# OS_Siding_Board_schematic.net
KiCad netlist of a schematic drawn in EasyEDA
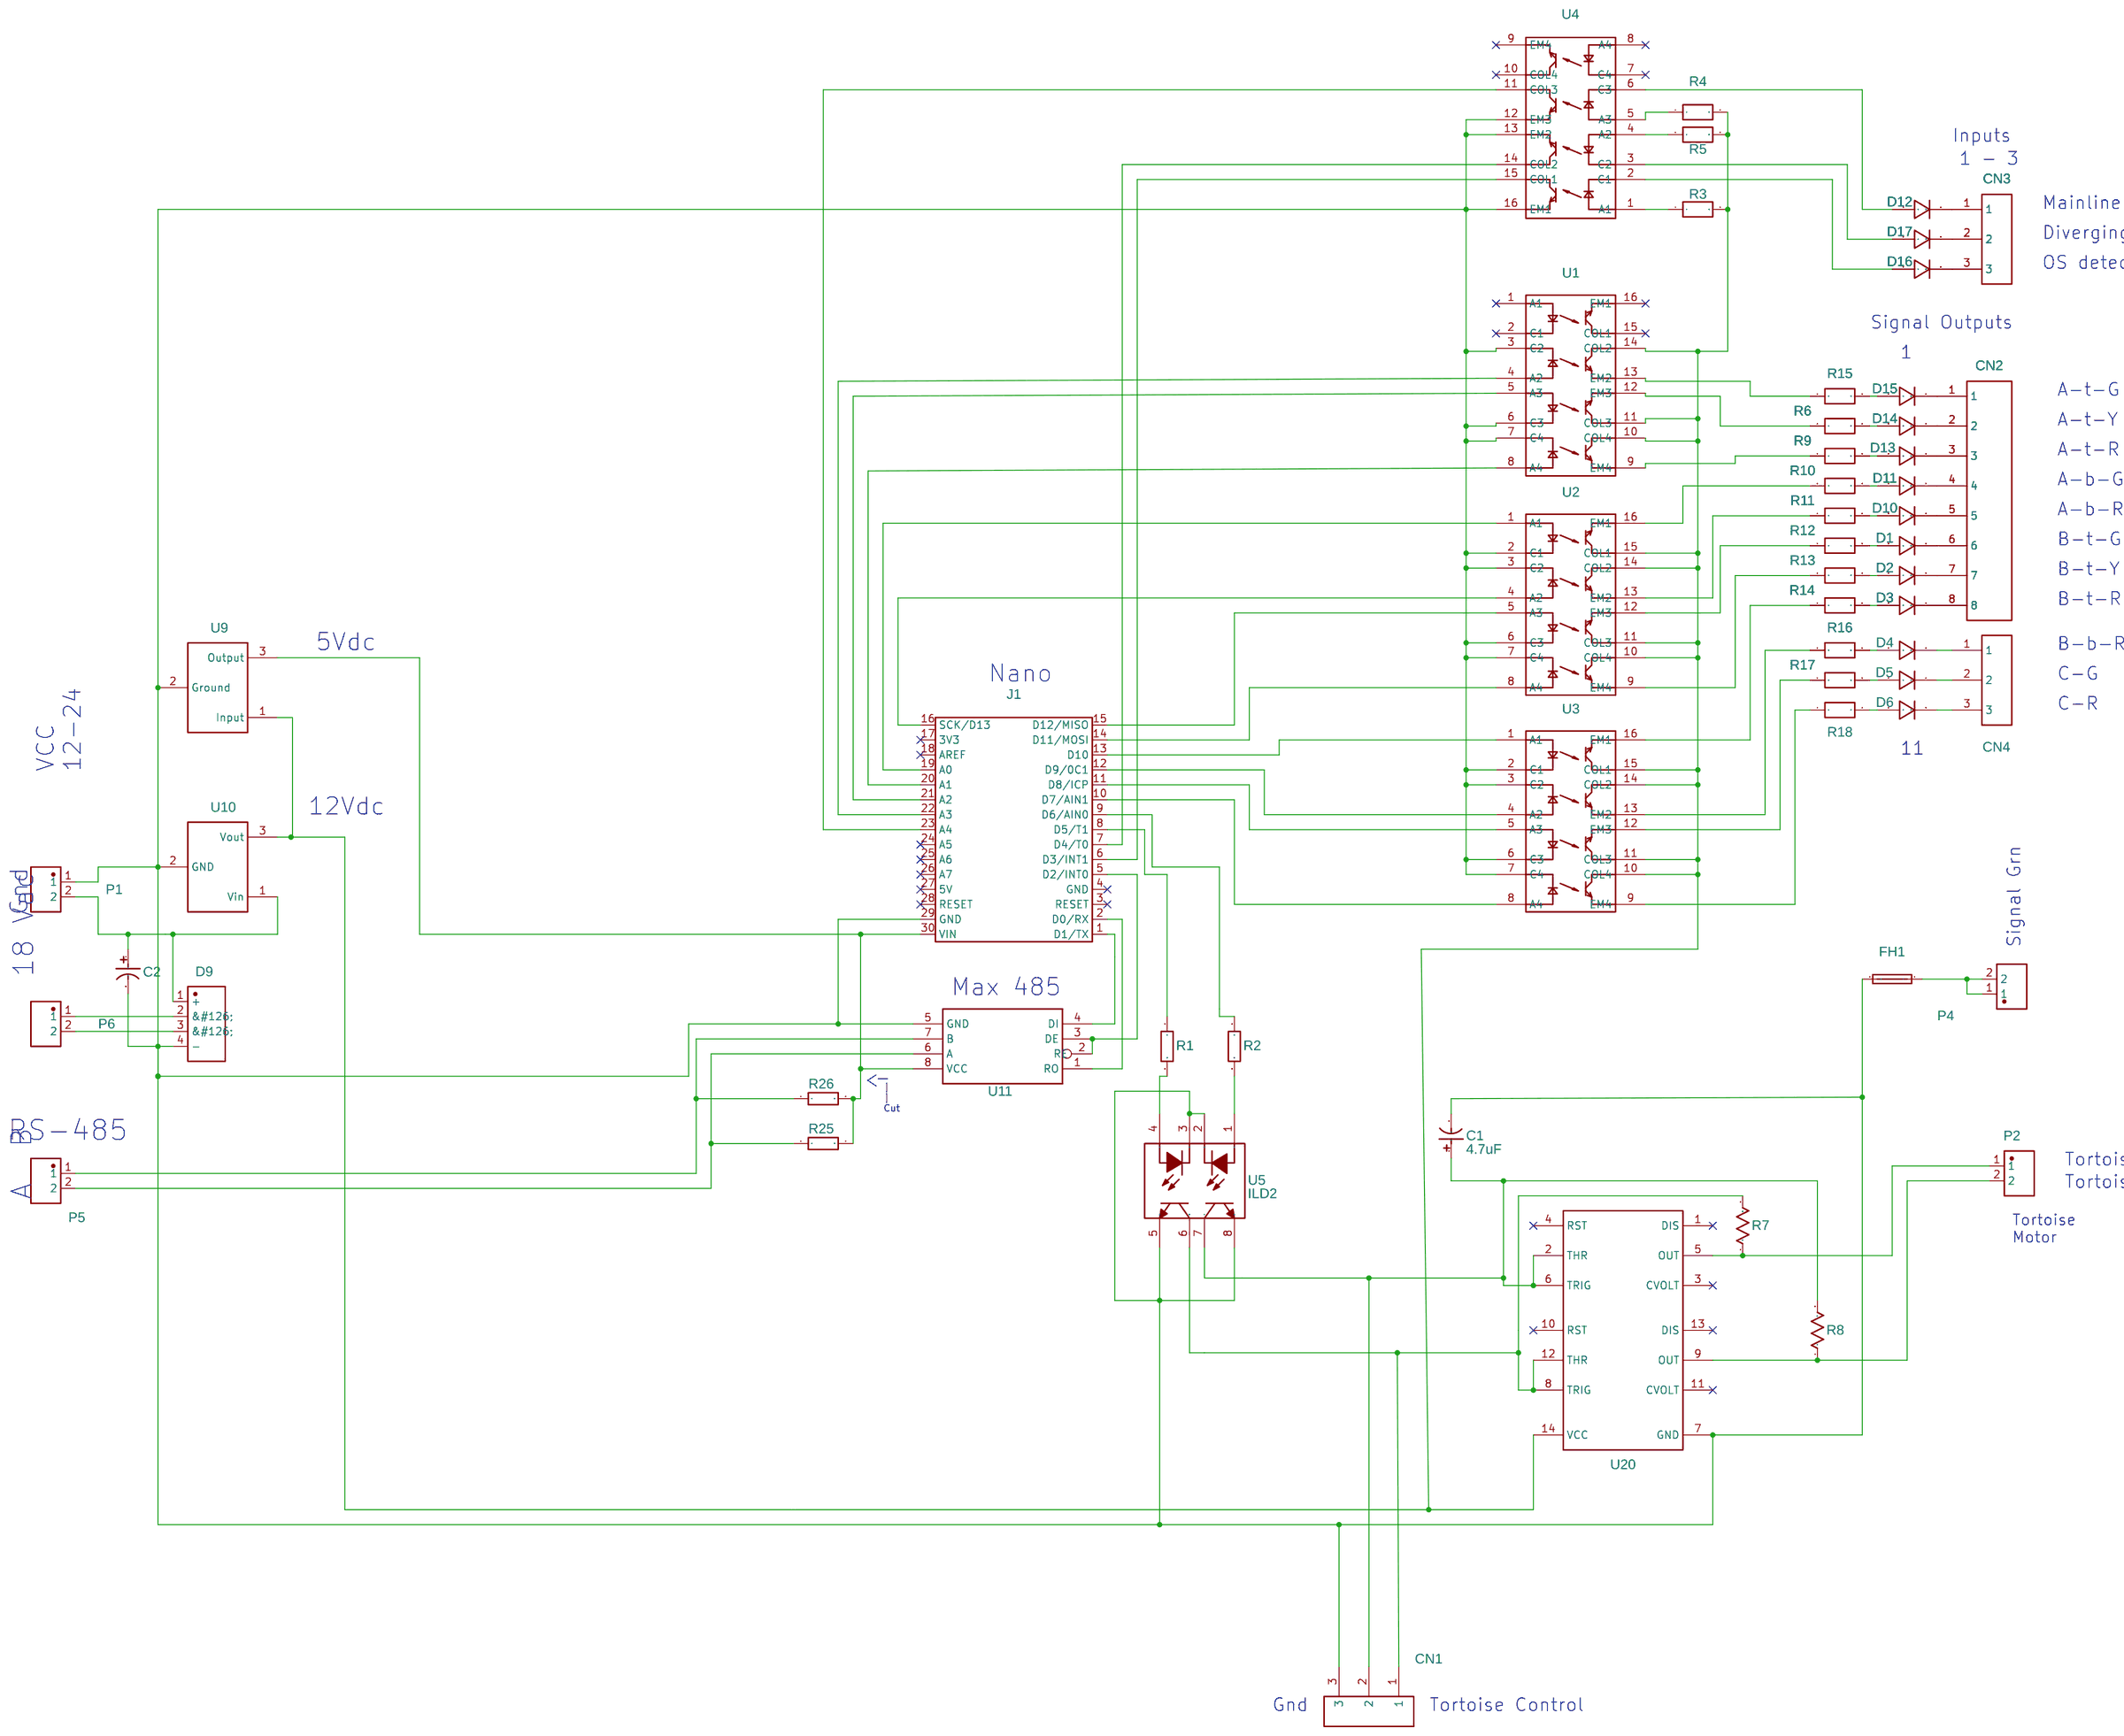
[diagram p0: schematic sheet]

(export (version "E")
  (design (tool "Eeschema 10.0.6"))
  (components
    (comp (ref "C1")
      (value "4.7uF")
      (fields
        (field (name "BOM_Manufacturer Part") "4.7uF 50V 4*7")
        (field (name "BOM_Supplier Part") "C43841")
      )
      (libsource (lib "") (part "4.7uF 50V 4*7"))
    )
    (comp (ref "C2")
      (value "470uF")
      (fields
        (field (name "BOM_Manufacturer Part") "470uF 100V 16*25")
        (field (name "BOM_Supplier Part") "C72551")
      )
      (libsource (lib "") (part "470uF 100V 16*25"))
    )
    (comp (ref "CN1")
      (value "WJ25C-B-7.62-3P-13-00A")
      (fields (field (name "BOM_Supplier Part") "C61583"))
      (libsource (lib "") (part "WJ25C-B-7.62-3P-13-00A_1"))
    )
    (comp (ref "CN2")
      (value "WJ25C-B-7.62-8P-13-00A")
      (fields (field (name "BOM_Supplier Part") "C49492"))
      (libsource (lib "") (part "Unknown_1245_155"))
    )
    (comp (ref "CN3")
      (value "WJ25C-B-7.62-3P-13-00A")
      (fields (field (name "BOM_Supplier Part") "C61583"))
      (libsource (lib "") (part "WJ25C-B-7.62-3P-13-00A"))
    )
    (comp (ref "CN4")
      (value "WJ25C-B-7.62-3P-13-00A")
      (fields (field (name "BOM_Supplier Part") "C61583"))
      (libsource (lib "") (part "WJ25C-B-7.62-3P-13-00A"))
    )
    (comp (ref "D1")
      (value "1N4001")
      (fields (field (name "BOM_Supplier Part") "C169150"))
      (libsource (lib "") (part "Unknown_1205_185"))
    )
    (comp (ref "D2")
      (value "1N4001")
      (fields (field (name "BOM_Supplier Part") "C169150"))
      (libsource (lib "") (part "Unknown_1205_205"))
    )
    (comp (ref "D3")
      (value "1N4001")
      (fields (field (name "BOM_Supplier Part") "C169150"))
      (libsource (lib "") (part "Unknown_1205_225"))
    )
    (comp (ref "D4")
      (value "1N4001")
      (fields (field (name "BOM_Supplier Part") "C169150"))
      (libsource (lib "") (part "Unknown_1205_255"))
    )
    (comp (ref "D5")
      (value "1N4001")
      (fields (field (name "BOM_Supplier Part") "C169150"))
      (libsource (lib "") (part "Unknown_1205_275"))
    )
    (comp (ref "D6")
      (value "1N4001")
      (fields (field (name "BOM_Supplier Part") "C169150"))
      (libsource (lib "") (part "Unknown_1205_295"))
    )
    (comp (ref "D9")
      (value "D50SB100")
      (fields (field (name "BOM_Supplier Part") "C411148"))
      (libsource (lib "") (part "Unknown_60_505"))
    )
    (comp (ref "D10")
      (value "1N4001")
      (fields (field (name "BOM_Supplier Part") "C169150"))
      (libsource (lib "") (part "Unknown_1205_165"))
    )
    (comp (ref "D11")
      (value "1N4001")
      (fields (field (name "BOM_Supplier Part") "C169150"))
      (libsource (lib "") (part "Unknown_1205_145"))
    )
    (comp (ref "D12")
      (value "1N4001")
      (fields (field (name "BOM_Supplier Part") "C169150"))
      (libsource (lib "") (part "Unknown_1215_-40"))
    )
    (comp (ref "D13")
      (value "1N4001")
      (fields (field (name "BOM_Supplier Part") "C169150"))
      (libsource (lib "") (part "Unknown_1205_125"))
    )
    (comp (ref "D14")
      (value "1N4001")
      (fields (field (name "BOM_Supplier Part") "C169150"))
      (libsource (lib "") (part "Unknown_1205_105"))
    )
    (comp (ref "D15")
      (value "1N4001")
      (fields (field (name "BOM_Supplier Part") "C169150"))
      (libsource (lib "") (part "Unknown_1205_85"))
    )
    (comp (ref "D16")
      (value "1N4001")
      (fields (field (name "BOM_Supplier Part") "C169150"))
      (libsource (lib "") (part "Unknown_1215_0"))
    )
    (comp (ref "D17")
      (value "1N4001")
      (fields (field (name "BOM_Supplier Part") "C169150"))
      (libsource (lib "") (part "Unknown_1215_-20"))
    )
    (comp (ref "FH1")
      (value "64600001003")
      (fields (field (name "BOM_Supplier Part") "C206887"))
      (libsource (lib "") (part "Unknown_1195_475"))
    )
    (comp (ref "J1") (value "Arduino_Nano_Header") (libsource (lib "") (part "Unknown_605_375")))
    (comp (ref "P1")
      (value "WJ25C-B-2P")
      (fields (field (name "BOM_Supplier Part") "C8422"))
      (libsource (lib "") (part "Unknown_-40_415"))
    )
    (comp (ref "P2")
      (value "WJ25C-B-2P")
      (fields (field (name "BOM_Supplier Part") "C8422"))
      (libsource (lib "") (part "Unknown_1280_605"))
    )
    (comp (ref "P4")
      (value "WJ25C-B-2P")
      (fields (field (name "BOM_Supplier Part") "C8422"))
      (libsource (lib "") (part "Unknown_1275_480"))
    )
    (comp (ref "P5")
      (value "WJ25C-B-2P")
      (fields (field (name "BOM_Supplier Part") "C8422"))
      (libsource (lib "") (part "Unknown_-40_610"))
    )
    (comp (ref "P6")
      (value "WJ25C-B-2P")
      (fields (field (name "BOM_Supplier Part") "C8422"))
      (libsource (lib "") (part "Unknown_-40_505"))
    )
    (comp (ref "R1")
      (value "150")
      (fields
        (field (name "BOM_Manufacturer Part") "CFR0W4J0151A50")
        (field (name "BOM_Supplier Part") "C70814")
      )
      (libsource (lib "") (part "CFR0W4J0151A50"))
    )
    (comp (ref "R2")
      (value "150")
      (fields
        (field (name "BOM_Manufacturer Part") "CFR0W4J0151A50")
        (field (name "BOM_Supplier Part") "C70814")
      )
      (libsource (lib "") (part "CFR0W4J0151A50"))
    )
    (comp (ref "R3")
      (value "680")
      (fields
        (field (name "BOM_Manufacturer Part") "RD 1/4W 680R J T/B A1")
        (field (name "BOM_Supplier Part") "C433698")
      )
      (libsource (lib "") (part "RD 1/4W 680R J T/B A1"))
    )
    (comp (ref "R4")
      (value "680")
      (fields
        (field (name "BOM_Manufacturer Part") "RD 1/4W 680R J T/B A1")
        (field (name "BOM_Supplier Part") "C433698")
      )
      (libsource (lib "") (part "RD 1/4W 680R J T/B A1"))
    )
    (comp (ref "R5")
      (value "680")
      (fields
        (field (name "BOM_Manufacturer Part") "RD 1/4W 680R J T/B A1")
        (field (name "BOM_Supplier Part") "C433698")
      )
      (libsource (lib "") (part "RD 1/4W 680R J T/B A1"))
    )
    (comp (ref "R6")
      (value "390")
      (fields
        (field (name "BOM_Manufacturer Part") "RD 1/4W 390R J T/B A1")
        (field (name "BOM_Supplier Part") "C433722")
      )
      (libsource (lib "") (part "RD 1/4W 390R J T/B A1"))
    )
    (comp (ref "R7")
      (value "10k")
      (fields
        (field (name "BOM_Manufacturer Part") "RESISTOR_ALONG")
        (field (name "BOM_Supplier Part") "9339116")
      )
      (libsource (lib "") (part "Unknown_1095_640"))
    )
    (comp (ref "R8")
      (value "10k")
      (fields
        (field (name "BOM_Manufacturer Part") "RESISTOR_ALONG")
        (field (name "BOM_Supplier Part") "9339116")
      )
      (libsource (lib "") (part "Unknown_1145_710"))
    )
    (comp (ref "R9")
      (value "390")
      (fields
        (field (name "BOM_Manufacturer Part") "RD 1/4W 390R J T/B A1")
        (field (name "BOM_Supplier Part") "C433722")
      )
      (libsource (lib "") (part "RD 1/4W 390R J T/B A1"))
    )
    (comp (ref "R10")
      (value "390")
      (fields
        (field (name "BOM_Manufacturer Part") "RD 1/4W 390R J T/B A1")
        (field (name "BOM_Supplier Part") "C433722")
      )
      (libsource (lib "") (part "RD 1/4W 390R J T/B A1"))
    )
    (comp (ref "R11")
      (value "390")
      (fields
        (field (name "BOM_Manufacturer Part") "RD 1/4W 390R J T/B A1")
        (field (name "BOM_Supplier Part") "C433722")
      )
      (libsource (lib "") (part "RD 1/4W 390R J T/B A1"))
    )
    (comp (ref "R12")
      (value "390")
      (fields
        (field (name "BOM_Manufacturer Part") "RD 1/4W 390R J T/B A1")
        (field (name "BOM_Supplier Part") "C433722")
      )
      (libsource (lib "") (part "RD 1/4W 390R J T/B A1"))
    )
    (comp (ref "R13")
      (value "390")
      (fields
        (field (name "BOM_Manufacturer Part") "RD 1/4W 390R J T/B A1")
        (field (name "BOM_Supplier Part") "C433722")
      )
      (libsource (lib "") (part "RD 1/4W 390R J T/B A1"))
    )
    (comp (ref "R14")
      (value "390")
      (fields
        (field (name "BOM_Manufacturer Part") "RD 1/4W 390R J T/B A1")
        (field (name "BOM_Supplier Part") "C433722")
      )
      (libsource (lib "") (part "RD 1/4W 390R J T/B A1"))
    )
    (comp (ref "R15")
      (value "390")
      (fields
        (field (name "BOM_Manufacturer Part") "RD 1/4W 390R J T/B A1")
        (field (name "BOM_Supplier Part") "C433722")
      )
      (libsource (lib "") (part "RD 1/4W 390R J T/B A1"))
    )
    (comp (ref "R16")
      (value "390")
      (fields
        (field (name "BOM_Manufacturer Part") "RD 1/4W 390R J T/B A1")
        (field (name "BOM_Supplier Part") "C433722")
      )
      (libsource (lib "") (part "RD 1/4W 390R J T/B A1"))
    )
    (comp (ref "R17")
      (value "390")
      (fields
        (field (name "BOM_Manufacturer Part") "RD 1/4W 390R J T/B A1")
        (field (name "BOM_Supplier Part") "C433722")
      )
      (libsource (lib "") (part "RD 1/4W 390R J T/B A1"))
    )
    (comp (ref "R18")
      (value "390")
      (fields
        (field (name "BOM_Manufacturer Part") "RD 1/4W 390R J T/B A1")
        (field (name "BOM_Supplier Part") "C433722")
      )
      (libsource (lib "") (part "RD 1/4W 390R J T/B A1"))
    )
    (comp (ref "R25")
      (value "10K")
      (fields
        (field (name "BOM_Manufacturer Part") "CFR0W4J0103A50")
        (field (name "BOM_Supplier Part") "C61299")
      )
      (libsource (lib "") (part "CFR0W4J0103A50"))
    )
    (comp (ref "R26")
      (value "10K")
      (fields
        (field (name "BOM_Manufacturer Part") "CFR0W4J0103A50")
        (field (name "BOM_Supplier Part") "C61299")
      )
      (libsource (lib "") (part "CFR0W4J0103A50"))
    )
    (comp (ref "U1")
      (value "ILQ2")
      (fields (field (name "BOM_Supplier Part") "C145338"))
      (libsource (lib "") (part "ILQ2_1"))
    )
    (comp (ref "U2")
      (value "ILQ2")
      (fields (field (name "BOM_Supplier Part") "C145338"))
      (libsource (lib "") (part "ILQ2"))
    )
    (comp (ref "U3")
      (value "ILQ2")
      (fields (field (name "BOM_Supplier Part") "C145338"))
      (libsource (lib "") (part "ILQ2"))
    )
    (comp (ref "U4")
      (value "ILQ2")
      (fields (field (name "BOM_Supplier Part") "C145338"))
      (libsource (lib "") (part "ILQ2_2"))
    )
    (comp (ref "U5")
      (value "ILD2")
      (fields (field (name "BOM_Supplier Part") "C10612"))
      (libsource (lib "") (part "ILD2"))
    )
    (comp (ref "U9")
      (value "MC7805BTG")
      (fields (field (name "BOM_Supplier Part") "C45385"))
      (libsource (lib "") (part "Unknown_75_280"))
    )
    (comp (ref "U10")
      (value "CJ7812")
      (fields (field (name "BOM_Supplier Part") "C77894"))
      (libsource (lib "") (part "Unknown_75_400"))
    )
    (comp (ref "U11") (value "MAX485DIL") (libsource (lib "") (part "Unknown_600_520")))
    (comp (ref "U20")
      (value "LM556CN")
      (fields (field (name "BOM_Manufacturer Part") "?"))
      (libsource (lib "") (part "Unknown_1015_710"))
    )
  )
  (nets
    (net (code "1") (name "Net-(C1-Pad1)") (class "Default")
      (node (ref "C1") (pin "1") (pinfunction "1_1") (pintype "input"))
      (node (ref "CN1") (pin "2") (pinfunction "2_2") (pintype "input"))
      (node (ref "R8") (pin "2") (pinfunction "2_2") (pintype "unspecified"))
      (node (ref "U20") (pin "2") (pinfunction "THR_2") (pintype "unspecified"))
      (node (ref "U20") (pin "6") (pinfunction "TRIG_6") (pintype "unspecified"))
      (node (ref "U5") (pin "7") (pinfunction "7_7") (pintype "unspecified"))
    )
    (net (code "2") (name "Net-(CN1-Pad1)") (class "Default")
      (node (ref "CN1") (pin "1") (pinfunction "1_1") (pintype "input"))
      (node (ref "R7") (pin "2") (pinfunction "2_2") (pintype "unspecified"))
      (node (ref "U20") (pin "12") (pinfunction "THR_12") (pintype "unspecified"))
      (node (ref "U20") (pin "8") (pinfunction "TRIG_8") (pintype "unspecified"))
      (node (ref "U5") (pin "6") (pinfunction "6_6") (pintype "unspecified"))
    )
    (net (code "3") (name "Net-(CN2-Pad1)") (class "Default")
      (node (ref "CN2") (pin "1") (pinfunction "1_1") (pintype "input"))
      (node (ref "D15") (pin "2") (pinfunction "2_2") (pintype "unspecified"))
    )
    (net (code "4") (name "Net-(CN2-Pad2)") (class "Default")
      (node (ref "CN2") (pin "2") (pinfunction "2_2") (pintype "input"))
      (node (ref "D14") (pin "2") (pinfunction "2_2") (pintype "unspecified"))
    )
    (net (code "5") (name "Net-(CN2-Pad3)") (class "Default")
      (node (ref "CN2") (pin "3") (pinfunction "3_3") (pintype "input"))
      (node (ref "D13") (pin "2") (pinfunction "2_2") (pintype "unspecified"))
    )
    (net (code "6") (name "Net-(CN2-Pad4)") (class "Default")
      (node (ref "CN2") (pin "4") (pinfunction "4_4") (pintype "input"))
      (node (ref "D11") (pin "2") (pinfunction "2_2") (pintype "unspecified"))
    )
    (net (code "7") (name "Net-(CN2-Pad5)") (class "Default")
      (node (ref "CN2") (pin "5") (pinfunction "5_5") (pintype "input"))
      (node (ref "D10") (pin "2") (pinfunction "2_2") (pintype "unspecified"))
    )
    (net (code "8") (name "Net-(CN2-Pad6)") (class "Default")
      (node (ref "CN2") (pin "6") (pinfunction "6_6") (pintype "input"))
      (node (ref "D1") (pin "2") (pinfunction "2_2") (pintype "unspecified"))
    )
    (net (code "9") (name "Net-(CN2-Pad7)") (class "Default")
      (node (ref "CN2") (pin "7") (pinfunction "7_7") (pintype "input"))
      (node (ref "D2") (pin "2") (pinfunction "2_2") (pintype "unspecified"))
    )
    (net (code "10") (name "Net-(CN2-Pad8)") (class "Default")
      (node (ref "CN2") (pin "8") (pinfunction "8_8") (pintype "input"))
      (node (ref "D3") (pin "2") (pinfunction "2_2") (pintype "unspecified"))
    )
    (net (code "11") (name "Net-(CN3-Pad1)") (class "Default")
      (node (ref "CN3") (pin "1") (pinfunction "1_1") (pintype "input"))
      (node (ref "D12") (pin "2") (pinfunction "2_2") (pintype "unspecified"))
    )
    (net (code "12") (name "Net-(CN3-Pad2)") (class "Default")
      (node (ref "CN3") (pin "2") (pinfunction "2_2") (pintype "input"))
      (node (ref "D17") (pin "2") (pinfunction "2_2") (pintype "unspecified"))
    )
    (net (code "13") (name "Net-(CN3-Pad3)") (class "Default")
      (node (ref "CN3") (pin "3") (pinfunction "3_3") (pintype "input"))
      (node (ref "D16") (pin "2") (pinfunction "2_2") (pintype "unspecified"))
    )
    (net (code "14") (name "Net-(CN4-Pad1)") (class "Default")
      (node (ref "CN4") (pin "1") (pinfunction "1_1") (pintype "input"))
      (node (ref "D4") (pin "2") (pinfunction "2_2") (pintype "unspecified"))
    )
    (net (code "15") (name "Net-(CN4-Pad2)") (class "Default")
      (node (ref "CN4") (pin "2") (pinfunction "2_2") (pintype "input"))
      (node (ref "D5") (pin "2") (pinfunction "2_2") (pintype "unspecified"))
    )
    (net (code "16") (name "Net-(CN4-Pad3)") (class "Default")
      (node (ref "CN4") (pin "3") (pinfunction "3_3") (pintype "input"))
      (node (ref "D6") (pin "2") (pinfunction "2_2") (pintype "unspecified"))
    )
    (net (code "17") (name "Net-(D1-Pad1)") (class "Default")
      (node (ref "D1") (pin "1") (pinfunction "1_1") (pintype "unspecified"))
      (node (ref "R12") (pin "2") (pinfunction "2_2") (pintype "unspecified"))
    )
    (net (code "18") (name "Net-(D2-Pad1)") (class "Default")
      (node (ref "D2") (pin "1") (pinfunction "1_1") (pintype "unspecified"))
      (node (ref "R13") (pin "2") (pinfunction "2_2") (pintype "unspecified"))
    )
    (net (code "19") (name "Net-(D3-Pad1)") (class "Default")
      (node (ref "D3") (pin "1") (pinfunction "1_1") (pintype "unspecified"))
      (node (ref "R14") (pin "2") (pinfunction "2_2") (pintype "unspecified"))
    )
    (net (code "20") (name "Net-(D4-Pad1)") (class "Default")
      (node (ref "D4") (pin "1") (pinfunction "1_1") (pintype "unspecified"))
      (node (ref "R16") (pin "2") (pinfunction "2_2") (pintype "unspecified"))
    )
    (net (code "21") (name "Net-(D5-Pad1)") (class "Default")
      (node (ref "D5") (pin "1") (pinfunction "1_1") (pintype "unspecified"))
      (node (ref "R17") (pin "2") (pinfunction "2_2") (pintype "unspecified"))
    )
    (net (code "22") (name "Net-(D6-Pad1)") (class "Default")
      (node (ref "D6") (pin "1") (pinfunction "1_1") (pintype "unspecified"))
      (node (ref "R18") (pin "2") (pinfunction "2_2") (pintype "unspecified"))
    )
    (net (code "23") (name "Net-(D9-&#126;-Pad2)") (class "Default")
      (node (ref "D9") (pin "2") (pinfunction "&#126;_2") (pintype "unspecified"))
      (node (ref "P6") (pin "1") (pinfunction "1_1") (pintype "unspecified"))
    )
    (net (code "24") (name "Net-(D9-&#126;-Pad3)") (class "Default")
      (node (ref "D9") (pin "3") (pinfunction "&#126;_3") (pintype "unspecified"))
      (node (ref "P6") (pin "2") (pinfunction "2_2") (pintype "unspecified"))
    )
    (net (code "25") (name "Net-(D9-+)") (class "Default")
      (node (ref "C2") (pin "1") (pinfunction "1_1") (pintype "input"))
      (node (ref "D9") (pin "1") (pinfunction "+_1") (pintype "unspecified"))
      (node (ref "P1") (pin "2") (pinfunction "2_2") (pintype "unspecified"))
      (node (ref "U10") (pin "1") (pinfunction "Vin_1") (pintype "unspecified"))
    )
    (net (code "26") (name "Net-(D9--)") (class "Default")
      (node (ref "C1") (pin "2") (pinfunction "2_2") (pintype "input"))
      (node (ref "C2") (pin "2") (pinfunction "2_2") (pintype "input"))
      (node (ref "CN1") (pin "3") (pinfunction "3_3") (pintype "input"))
      (node (ref "D9") (pin "4") (pinfunction "-_4") (pintype "unspecified"))
      (node (ref "FH1") (pin "2") (pinfunction "2_2") (pintype "unspecified"))
      (node (ref "J1") (pin "29") (pinfunction "GND_29") (pintype "unspecified"))
      (node (ref "P1") (pin "1") (pinfunction "1_1") (pintype "unspecified"))
      (node (ref "U1") (pin "3") (pinfunction "C2_3") (pintype "unspecified"))
      (node (ref "U1") (pin "6") (pinfunction "C3_6") (pintype "unspecified"))
      (node (ref "U1") (pin "7") (pinfunction "C4_7") (pintype "unspecified"))
      (node (ref "U10") (pin "2") (pinfunction "GND_2") (pintype "unspecified"))
      (node (ref "U11") (pin "5") (pinfunction "GND_5") (pintype "unspecified"))
      (node (ref "U2") (pin "2") (pinfunction "C1_2") (pintype "unspecified"))
      (node (ref "U2") (pin "3") (pinfunction "C2_3") (pintype "unspecified"))
      (node (ref "U2") (pin "6") (pinfunction "C3_6") (pintype "unspecified"))
      (node (ref "U2") (pin "7") (pinfunction "C4_7") (pintype "unspecified"))
      (node (ref "U20") (pin "7") (pinfunction "GND_7") (pintype "passive"))
      (node (ref "U3") (pin "2") (pinfunction "C1_2") (pintype "unspecified"))
      (node (ref "U3") (pin "3") (pinfunction "C2_3") (pintype "unspecified"))
      (node (ref "U3") (pin "6") (pinfunction "C3_6") (pintype "unspecified"))
      (node (ref "U3") (pin "7") (pinfunction "C4_7") (pintype "unspecified"))
      (node (ref "U4") (pin "12") (pinfunction "EM3_12") (pintype "unspecified"))
      (node (ref "U4") (pin "13") (pinfunction "EM2_13") (pintype "unspecified"))
      (node (ref "U4") (pin "16") (pinfunction "EM1_16") (pintype "unspecified"))
      (node (ref "U5") (pin "2") (pinfunction "2_2") (pintype "unspecified"))
      (node (ref "U5") (pin "3") (pinfunction "3_3") (pintype "unspecified"))
      (node (ref "U5") (pin "5") (pinfunction "5_5") (pintype "unspecified"))
      (node (ref "U5") (pin "8") (pinfunction "8_8") (pintype "unspecified"))
      (node (ref "U9") (pin "2") (pinfunction "Ground_2") (pintype "unspecified"))
    )
    (net (code "27") (name "Net-(D10-Pad1)") (class "Default")
      (node (ref "D10") (pin "1") (pinfunction "1_1") (pintype "unspecified"))
      (node (ref "R11") (pin "2") (pinfunction "2_2") (pintype "unspecified"))
    )
    (net (code "28") (name "Net-(D11-Pad1)") (class "Default")
      (node (ref "D11") (pin "1") (pinfunction "1_1") (pintype "unspecified"))
      (node (ref "R10") (pin "2") (pinfunction "2_2") (pintype "unspecified"))
    )
    (net (code "29") (name "Net-(D13-Pad1)") (class "Default")
      (node (ref "D13") (pin "1") (pinfunction "1_1") (pintype "unspecified"))
      (node (ref "R9") (pin "2") (pinfunction "2_2") (pintype "unspecified"))
    )
    (net (code "30") (name "Net-(D14-Pad1)") (class "Default")
      (node (ref "D14") (pin "1") (pinfunction "1_1") (pintype "unspecified"))
      (node (ref "R6") (pin "2") (pinfunction "2_2") (pintype "unspecified"))
    )
    (net (code "31") (name "Net-(D15-Pad1)") (class "Default")
      (node (ref "D15") (pin "1") (pinfunction "1_1") (pintype "unspecified"))
      (node (ref "R15") (pin "2") (pinfunction "2_2") (pintype "unspecified"))
    )
    (net (code "32") (name "Net-(FH1-Pad1)") (class "Default")
      (node (ref "FH1") (pin "1") (pinfunction "1_1") (pintype "unspecified"))
      (node (ref "P4") (pin "1") (pinfunction "1_1") (pintype "unspecified"))
      (node (ref "P4") (pin "2") (pinfunction "2_2") (pintype "unspecified"))
    )
    (net (code "33") (name "Net-(J1-A0)") (class "Default")
      (node (ref "J1") (pin "19") (pinfunction "A0_19") (pintype "unspecified"))
      (node (ref "U2") (pin "1") (pinfunction "A1_1") (pintype "unspecified"))
    )
    (net (code "34") (name "Net-(J1-A1)") (class "Default")
      (node (ref "J1") (pin "20") (pinfunction "A1_20") (pintype "unspecified"))
      (node (ref "U1") (pin "8") (pinfunction "A4_8") (pintype "unspecified"))
    )
    (net (code "35") (name "Net-(J1-A2)") (class "Default")
      (node (ref "J1") (pin "21") (pinfunction "A2_21") (pintype "unspecified"))
      (node (ref "U1") (pin "5") (pinfunction "A3_5") (pintype "unspecified"))
    )
    (net (code "36") (name "Net-(J1-A3)") (class "Default")
      (node (ref "J1") (pin "22") (pinfunction "A3_22") (pintype "unspecified"))
      (node (ref "U1") (pin "4") (pinfunction "A2_4") (pintype "unspecified"))
    )
    (net (code "37") (name "Net-(J1-A4)") (class "Default")
      (node (ref "J1") (pin "23") (pinfunction "A4_23") (pintype "unspecified"))
      (node (ref "U4") (pin "11") (pinfunction "COL3_11") (pintype "unspecified"))
    )
    (net (code "38") (name "Net-(J1-D0{slash}RX)") (class "Default")
      (node (ref "J1") (pin "2") (pinfunction "D0/RX_2") (pintype "unspecified"))
      (node (ref "U11") (pin "1") (pinfunction "RO_1") (pintype "unspecified"))
    )
    (net (code "39") (name "Net-(J1-D1{slash}TX)") (class "Default")
      (node (ref "J1") (pin "1") (pinfunction "D1/TX_1") (pintype "unspecified"))
      (node (ref "U11") (pin "4") (pinfunction "DI_4") (pintype "unspecified"))
    )
    (net (code "40") (name "Net-(J1-D2{slash}INT0)") (class "Default")
      (node (ref "J1") (pin "5") (pinfunction "D2/INT0_5") (pintype "unspecified"))
      (node (ref "U11") (pin "2") (pinfunction "RE_2") (pintype "unspecified"))
      (node (ref "U11") (pin "3") (pinfunction "DE_3") (pintype "unspecified"))
    )
    (net (code "41") (name "Net-(J1-D3{slash}INT1)") (class "Default")
      (node (ref "J1") (pin "6") (pinfunction "D3/INT1_6") (pintype "unspecified"))
      (node (ref "U4") (pin "15") (pinfunction "COL1_15") (pintype "unspecified"))
    )
    (net (code "42") (name "Net-(J1-D4{slash}T0)") (class "Default")
      (node (ref "J1") (pin "7") (pinfunction "D4/T0_7") (pintype "unspecified"))
      (node (ref "U4") (pin "14") (pinfunction "COL2_14") (pintype "unspecified"))
    )
    (net (code "43") (name "Net-(J1-D5{slash}T1)") (class "Default")
      (node (ref "J1") (pin "8") (pinfunction "D5/T1_8") (pintype "unspecified"))
      (node (ref "R1") (pin "1") (pinfunction "1_1") (pintype "input"))
    )
    (net (code "44") (name "Net-(J1-D6{slash}AIN0)") (class "Default")
      (node (ref "J1") (pin "9") (pinfunction "D6/AIN0_9") (pintype "unspecified"))
      (node (ref "R2") (pin "1") (pinfunction "1_1") (pintype "input"))
    )
    (net (code "45") (name "Net-(J1-D7{slash}AIN1)") (class "Default")
      (node (ref "J1") (pin "10") (pinfunction "D7/AIN1_10") (pintype "unspecified"))
      (node (ref "U3") (pin "8") (pinfunction "A4_8") (pintype "unspecified"))
    )
    (net (code "46") (name "Net-(J1-D8{slash}ICP)") (class "Default")
      (node (ref "J1") (pin "11") (pinfunction "D8/ICP_11") (pintype "unspecified"))
      (node (ref "U3") (pin "5") (pinfunction "A3_5") (pintype "unspecified"))
    )
    (net (code "47") (name "Net-(J1-D9{slash}0C1)") (class "Default")
      (node (ref "J1") (pin "12") (pinfunction "D9/0C1_12") (pintype "unspecified"))
      (node (ref "U3") (pin "4") (pinfunction "A2_4") (pintype "unspecified"))
    )
    (net (code "48") (name "Net-(J1-D10)") (class "Default")
      (node (ref "J1") (pin "13") (pinfunction "D10_13") (pintype "unspecified"))
      (node (ref "U3") (pin "1") (pinfunction "A1_1") (pintype "unspecified"))
    )
    (net (code "49") (name "Net-(J1-D11{slash}MOSI)") (class "Default")
      (node (ref "J1") (pin "14") (pinfunction "D11/MOSI_14") (pintype "unspecified"))
      (node (ref "U2") (pin "8") (pinfunction "A4_8") (pintype "unspecified"))
    )
    (net (code "50") (name "Net-(J1-D12{slash}MISO)") (class "Default")
      (node (ref "J1") (pin "15") (pinfunction "D12/MISO_15") (pintype "unspecified"))
      (node (ref "U2") (pin "5") (pinfunction "A3_5") (pintype "unspecified"))
    )
    (net (code "51") (name "Net-(J1-SCK{slash}D13)") (class "Default")
      (node (ref "J1") (pin "16") (pinfunction "SCK/D13_16") (pintype "unspecified"))
      (node (ref "U2") (pin "4") (pinfunction "A2_4") (pintype "unspecified"))
    )
    (net (code "52") (name "Net-(J1-VIN)") (class "Default")
      (node (ref "J1") (pin "30") (pinfunction "VIN_30") (pintype "unspecified"))
      (node (ref "R25") (pin "2") (pinfunction "2_2") (pintype "input"))
      (node (ref "R26") (pin "2") (pinfunction "2_2") (pintype "input"))
      (node (ref "U11") (pin "8") (pinfunction "VCC_8") (pintype "unspecified"))
      (node (ref "U9") (pin "3") (pinfunction "Output_3") (pintype "unspecified"))
    )
    (net (code "53") (name "Net-(P2-Pad1)") (class "Default")
      (node (ref "P2") (pin "1") (pinfunction "1_1") (pintype "unspecified"))
      (node (ref "R7") (pin "1") (pinfunction "1_1") (pintype "unspecified"))
      (node (ref "U20") (pin "5") (pinfunction "OUT_5") (pintype "output"))
    )
    (net (code "54") (name "Net-(P2-Pad2)") (class "Default")
      (node (ref "P2") (pin "2") (pinfunction "2_2") (pintype "unspecified"))
      (node (ref "R8") (pin "1") (pinfunction "1_1") (pintype "unspecified"))
      (node (ref "U20") (pin "9") (pinfunction "OUT_9") (pintype "output"))
    )
    (net (code "55") (name "Net-(R1-Pad2)") (class "Default")
      (node (ref "R1") (pin "2") (pinfunction "2_2") (pintype "input"))
      (node (ref "U5") (pin "4") (pinfunction "4_4") (pintype "unspecified"))
    )
    (net (code "56") (name "Net-(R2-Pad2)") (class "Default")
      (node (ref "R2") (pin "2") (pinfunction "2_2") (pintype "input"))
      (node (ref "U5") (pin "1") (pinfunction "1_1") (pintype "unspecified"))
    )
    (net (code "57") (name "Net-(U1-COL2)") (class "Default")
      (node (ref "R3") (pin "2") (pinfunction "2_2") (pintype "unspecified"))
      (node (ref "R4") (pin "2") (pinfunction "2_2") (pintype "unspecified"))
      (node (ref "R5") (pin "2") (pinfunction "2_2") (pintype "unspecified"))
      (node (ref "U1") (pin "10") (pinfunction "COL4_10") (pintype "unspecified"))
      (node (ref "U1") (pin "11") (pinfunction "COL3_11") (pintype "unspecified"))
      (node (ref "U1") (pin "14") (pinfunction "COL2_14") (pintype "unspecified"))
      (node (ref "U10") (pin "3") (pinfunction "Vout_3") (pintype "unspecified"))
      (node (ref "U2") (pin "10") (pinfunction "COL4_10") (pintype "unspecified"))
      (node (ref "U2") (pin "11") (pinfunction "COL3_11") (pintype "unspecified"))
      (node (ref "U2") (pin "14") (pinfunction "COL2_14") (pintype "unspecified"))
      (node (ref "U2") (pin "15") (pinfunction "COL1_15") (pintype "unspecified"))
      (node (ref "U20") (pin "14") (pinfunction "VCC_14") (pintype "passive"))
      (node (ref "U3") (pin "10") (pinfunction "COL4_10") (pintype "unspecified"))
      (node (ref "U3") (pin "11") (pinfunction "COL3_11") (pintype "unspecified"))
      (node (ref "U3") (pin "14") (pinfunction "COL2_14") (pintype "unspecified"))
      (node (ref "U3") (pin "15") (pinfunction "COL1_15") (pintype "unspecified"))
      (node (ref "U9") (pin "1") (pinfunction "Input_1") (pintype "unspecified"))
    )
    (net (code "58") (name "Net-(U1-EM2)") (class "Default")
      (node (ref "R15") (pin "1") (pinfunction "1_1") (pintype "unspecified"))
      (node (ref "U1") (pin "13") (pinfunction "EM2_13") (pintype "unspecified"))
    )
    (net (code "59") (name "Net-(U1-EM3)") (class "Default")
      (node (ref "R6") (pin "1") (pinfunction "1_1") (pintype "unspecified"))
      (node (ref "U1") (pin "12") (pinfunction "EM3_12") (pintype "unspecified"))
    )
    (net (code "60") (name "Net-(U1-EM4)") (class "Default")
      (node (ref "R9") (pin "1") (pinfunction "1_1") (pintype "unspecified"))
      (node (ref "U1") (pin "9") (pinfunction "EM4_9") (pintype "unspecified"))
    )
    (net (code "61") (name "Net-(U2-EM1)") (class "Default")
      (node (ref "R10") (pin "1") (pinfunction "1_1") (pintype "unspecified"))
      (node (ref "U2") (pin "16") (pinfunction "EM1_16") (pintype "unspecified"))
    )
    (net (code "62") (name "Net-(U2-EM2)") (class "Default")
      (node (ref "R11") (pin "1") (pinfunction "1_1") (pintype "unspecified"))
      (node (ref "U2") (pin "13") (pinfunction "EM2_13") (pintype "unspecified"))
    )
    (net (code "63") (name "Net-(U2-EM3)") (class "Default")
      (node (ref "R12") (pin "1") (pinfunction "1_1") (pintype "unspecified"))
      (node (ref "U2") (pin "12") (pinfunction "EM3_12") (pintype "unspecified"))
    )
    (net (code "64") (name "Net-(U2-EM4)") (class "Default")
      (node (ref "R13") (pin "1") (pinfunction "1_1") (pintype "unspecified"))
      (node (ref "U2") (pin "9") (pinfunction "EM4_9") (pintype "unspecified"))
    )
    (net (code "65") (name "Net-(U3-EM1)") (class "Default")
      (node (ref "R14") (pin "1") (pinfunction "1_1") (pintype "unspecified"))
      (node (ref "U3") (pin "16") (pinfunction "EM1_16") (pintype "unspecified"))
    )
    (net (code "66") (name "Net-(U3-EM2)") (class "Default")
      (node (ref "R16") (pin "1") (pinfunction "1_1") (pintype "unspecified"))
      (node (ref "U3") (pin "13") (pinfunction "EM2_13") (pintype "unspecified"))
    )
    (net (code "67") (name "Net-(U3-EM3)") (class "Default")
      (node (ref "R17") (pin "1") (pinfunction "1_1") (pintype "unspecified"))
      (node (ref "U3") (pin "12") (pinfunction "EM3_12") (pintype "unspecified"))
    )
    (net (code "68") (name "Net-(U3-EM4)") (class "Default")
      (node (ref "R18") (pin "1") (pinfunction "1_1") (pintype "unspecified"))
      (node (ref "U3") (pin "9") (pinfunction "EM4_9") (pintype "unspecified"))
    )
    (net (code "69") (name "Net-(U4-A1)") (class "Default")
      (node (ref "R3") (pin "1") (pinfunction "1_1") (pintype "unspecified"))
      (node (ref "U4") (pin "1") (pinfunction "A1_1") (pintype "unspecified"))
    )
    (net (code "70") (name "Net-(U4-A2)") (class "Default")
      (node (ref "R5") (pin "1") (pinfunction "1_1") (pintype "unspecified"))
      (node (ref "U4") (pin "4") (pinfunction "A2_4") (pintype "unspecified"))
    )
    (net (code "71") (name "Net-(U4-A3)") (class "Default")
      (node (ref "R4") (pin "1") (pinfunction "1_1") (pintype "unspecified"))
      (node (ref "U4") (pin "5") (pinfunction "A3_5") (pintype "unspecified"))
    )
    (net (code "72") (name "Net-(U4-C1)") (class "Default")
      (node (ref "D16") (pin "1") (pinfunction "1_1") (pintype "unspecified"))
      (node (ref "U4") (pin "2") (pinfunction "C1_2") (pintype "unspecified"))
    )
    (net (code "73") (name "Net-(U4-C2)") (class "Default")
      (node (ref "D17") (pin "1") (pinfunction "1_1") (pintype "unspecified"))
      (node (ref "U4") (pin "3") (pinfunction "C2_3") (pintype "unspecified"))
    )
    (net (code "74") (name "Net-(U4-C3)") (class "Default")
      (node (ref "D12") (pin "1") (pinfunction "1_1") (pintype "unspecified"))
      (node (ref "U4") (pin "6") (pinfunction "C3_6") (pintype "unspecified"))
    )
    (net (code "75") (name "Net-(U11-A)") (class "Default")
      (node (ref "P5") (pin "2") (pinfunction "2_2") (pintype "unspecified"))
      (node (ref "R25") (pin "1") (pinfunction "1_1") (pintype "input"))
      (node (ref "U11") (pin "6") (pinfunction "A_6") (pintype "unspecified"))
    )
    (net (code "76") (name "Net-(U11-B)") (class "Default")
      (node (ref "P5") (pin "1") (pinfunction "1_1") (pintype "unspecified"))
      (node (ref "R26") (pin "1") (pinfunction "1_1") (pintype "input"))
      (node (ref "U11") (pin "7") (pinfunction "B_7") (pintype "unspecified"))
    )
    (net (code "77") (name "unconnected-(J1-3V3-Pad17)") (class "Default")
      (node (ref "J1") (pin "17") (pinfunction "3V3_17") (pintype "unspecified+no_connect"))
    )
    (net (code "78") (name "unconnected-(J1-5V-Pad27)") (class "Default")
      (node (ref "J1") (pin "27") (pinfunction "5V_27") (pintype "unspecified+no_connect"))
    )
    (net (code "79") (name "unconnected-(J1-A5-Pad24)") (class "Default")
      (node (ref "J1") (pin "24") (pinfunction "A5_24") (pintype "unspecified+no_connect"))
    )
    (net (code "80") (name "unconnected-(J1-A6-Pad25)") (class "Default")
      (node (ref "J1") (pin "25") (pinfunction "A6_25") (pintype "unspecified+no_connect"))
    )
    (net (code "81") (name "unconnected-(J1-A7-Pad26)") (class "Default")
      (node (ref "J1") (pin "26") (pinfunction "A7_26") (pintype "unspecified+no_connect"))
    )
    (net (code "82") (name "unconnected-(J1-AREF-Pad18)") (class "Default")
      (node (ref "J1") (pin "18") (pinfunction "AREF_18") (pintype "unspecified+no_connect"))
    )
    (net (code "83") (name "unconnected-(J1-GND-Pad4)") (class "Default")
      (node (ref "J1") (pin "4") (pinfunction "GND_4") (pintype "unspecified+no_connect"))
    )
    (net (code "84") (name "unconnected-(J1-RESET-Pad3)") (class "Default")
      (node (ref "J1") (pin "3") (pinfunction "RESET_3") (pintype "unspecified+no_connect"))
    )
    (net (code "85") (name "unconnected-(J1-RESET-Pad28)") (class "Default")
      (node (ref "J1") (pin "28") (pinfunction "RESET_28") (pintype "unspecified+no_connect"))
    )
    (net (code "86") (name "unconnected-(U1-A1-Pad1)") (class "Default")
      (node (ref "U1") (pin "1") (pinfunction "A1_1") (pintype "unspecified+no_connect"))
    )
    (net (code "87") (name "unconnected-(U1-C1-Pad2)") (class "Default")
      (node (ref "U1") (pin "2") (pinfunction "C1_2") (pintype "unspecified+no_connect"))
    )
    (net (code "88") (name "unconnected-(U1-COL1-Pad15)") (class "Default")
      (node (ref "U1") (pin "15") (pinfunction "COL1_15") (pintype "unspecified+no_connect"))
    )
    (net (code "89") (name "unconnected-(U1-EM1-Pad16)") (class "Default")
      (node (ref "U1") (pin "16") (pinfunction "EM1_16") (pintype "unspecified+no_connect"))
    )
    (net (code "90") (name "unconnected-(U4-A4-Pad8)") (class "Default")
      (node (ref "U4") (pin "8") (pinfunction "A4_8") (pintype "unspecified+no_connect"))
    )
    (net (code "91") (name "unconnected-(U4-C4-Pad7)") (class "Default")
      (node (ref "U4") (pin "7") (pinfunction "C4_7") (pintype "unspecified+no_connect"))
    )
    (net (code "92") (name "unconnected-(U4-COL4-Pad10)") (class "Default")
      (node (ref "U4") (pin "10") (pinfunction "COL4_10") (pintype "unspecified+no_connect"))
    )
    (net (code "93") (name "unconnected-(U4-EM4-Pad9)") (class "Default")
      (node (ref "U4") (pin "9") (pinfunction "EM4_9") (pintype "unspecified+no_connect"))
    )
    (net (code "94") (name "unconnected-(U20-CVOLT-Pad3)") (class "Default")
      (node (ref "U20") (pin "3") (pinfunction "CVOLT_3") (pintype "unspecified+no_connect"))
    )
    (net (code "95") (name "unconnected-(U20-CVOLT-Pad11)") (class "Default")
      (node (ref "U20") (pin "11") (pinfunction "CVOLT_11") (pintype "unspecified+no_connect"))
    )
    (net (code "96") (name "unconnected-(U20-DIS-Pad1)") (class "Default")
      (node (ref "U20") (pin "1") (pinfunction "DIS_1") (pintype "unspecified+no_connect"))
    )
    (net (code "97") (name "unconnected-(U20-DIS-Pad13)") (class "Default")
      (node (ref "U20") (pin "13") (pinfunction "DIS_13") (pintype "unspecified+no_connect"))
    )
    (net (code "98") (name "unconnected-(U20-RST-Pad4)") (class "Default")
      (node (ref "U20") (pin "4") (pinfunction "RST_4") (pintype "unspecified+no_connect"))
    )
    (net (code "99") (name "unconnected-(U20-RST-Pad10)") (class "Default")
      (node (ref "U20") (pin "10") (pinfunction "RST_10") (pintype "unspecified+no_connect"))
    )
  )
)
